# zasilacz_v2.net
KiCad netlist of a schematic drawn in EAGLE
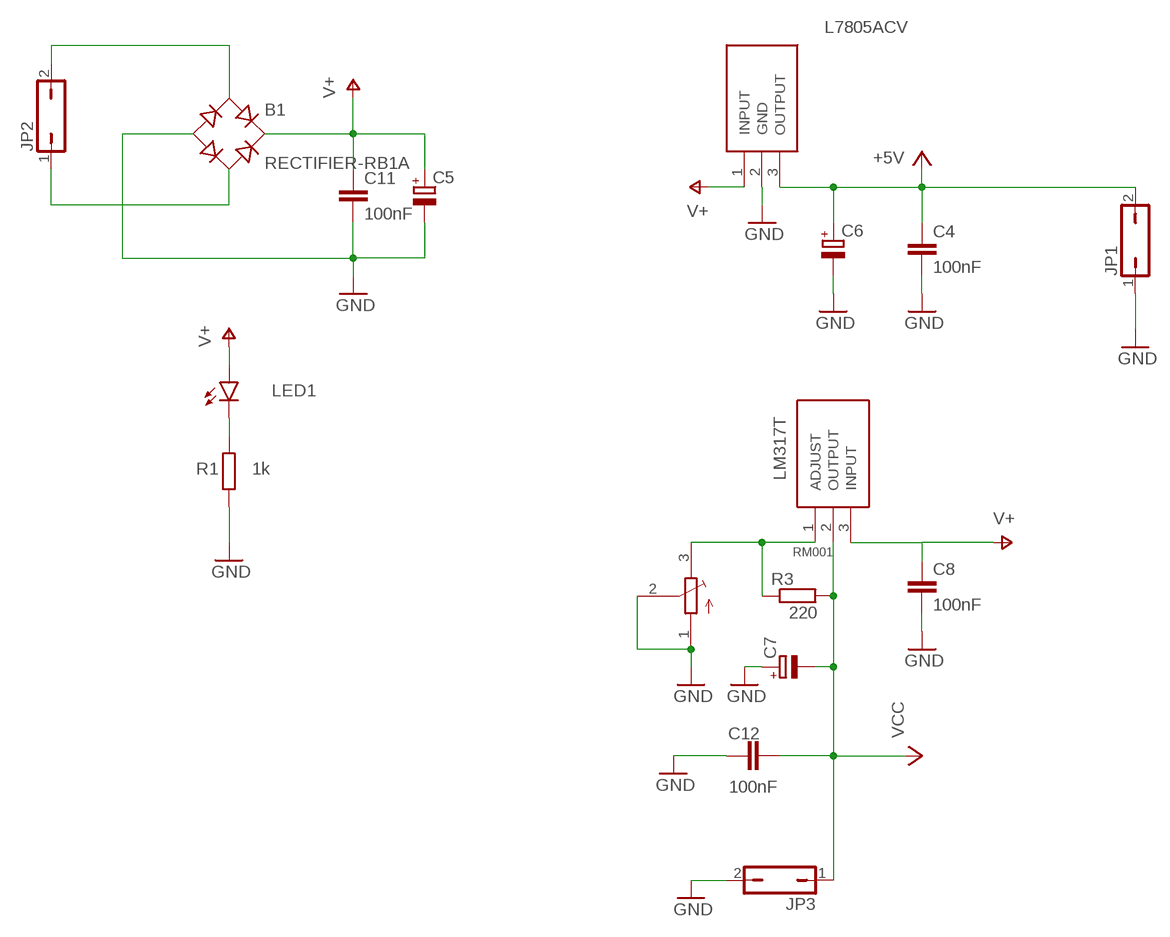
[diagram p0: schematic, sheet 1]

(export (version "E")
  (design (tool "Eeschema 10.0.6"))
  (components
    (comp (ref ",1")
      (value "LM317T")
      (footprint "eagle-import:TO255P460X1020X2008-3P")
      (fields (field (name "MOUSER_PART_NUMBER") "511-LM317T"))
      (libsource (lib "eagle-import") (part "LM317T"))
    )
    (comp (ref "B1")
      (value "RECTIFIER-RB1A")
      (footprint "eagle-import:RB1A")
      (libsource (lib "eagle-import") (part "RECTIFIER-RB1A"))
    )
    (comp (ref "C4")
      (value "100nF")
      (footprint "eagle-import:C025-024X044")
      (libsource (lib "eagle-import") (part "C-EU025-024X044"))
    )
    (comp (ref "C5")
      (value "CPOL-EUE5-10.5")
      (footprint "eagle-import:E5-10,5")
      (libsource (lib "eagle-import") (part "CPOL-EUE5-10.5"))
    )
    (comp (ref "C6")
      (value "CPOL-EUE5-10.5")
      (footprint "eagle-import:E5-10,5")
      (libsource (lib "eagle-import") (part "CPOL-EUE5-10.5"))
    )
    (comp (ref "C7")
      (value "CPOL-EUE5-10.5")
      (footprint "eagle-import:E5-10,5")
      (libsource (lib "eagle-import") (part "CPOL-EUE5-10.5"))
    )
    (comp (ref "C8")
      (value "100nF")
      (footprint "eagle-import:C025-024X044")
      (libsource (lib "eagle-import") (part "C-EU025-024X044"))
    )
    (comp (ref "C11")
      (value "100nF")
      (footprint "eagle-import:C025-024X044")
      (libsource (lib "eagle-import") (part "C-EU025-024X044"))
    )
    (comp (ref "C12")
      (value "100nF")
      (footprint "eagle-import:C025-024X044")
      (libsource (lib "eagle-import") (part "C-EU025-024X044"))
    )
    (comp (ref "IC1")
      (value "L7805ACV")
      (footprint "eagle-import:TO255P460X1020X2008-3P")
      (fields (field (name "MOUSER_PART_NUMBER") "511-L7805ACV"))
      (libsource (lib "eagle-import") (part "L7805ACV"))
    )
    (comp (ref "JP1")
      (value "JP1Q")
      (footprint "eagle-import:JP1")
      (libsource (lib "eagle-import") (part "JP1Q"))
    )
    (comp (ref "JP2")
      (value "JP1Q")
      (footprint "eagle-import:JP1")
      (libsource (lib "eagle-import") (part "JP1Q"))
    )
    (comp (ref "JP3")
      (value "JP1Q")
      (footprint "eagle-import:JP1")
      (libsource (lib "eagle-import") (part "JP1Q"))
    )
    (comp (ref "LED1")
      (value "TLLG4400")
      (footprint "eagle-import:LED3MM")
      (fields (field (name "MF") "VISHAY SEMICONDUCTOR"))
      (libsource (lib "eagle-import") (part "TLLG4400"))
    )
    (comp (ref "R1")
      (value "1k")
      (footprint "eagle-import:0204_5")
      (libsource (lib "eagle-import") (part "R-EU_0204/5"))
    )
    (comp (ref "R3")
      (value "220")
      (footprint "eagle-import:0204_5")
      (libsource (lib "eagle-import") (part "R-EU_0204/5"))
    )
    (comp (ref "RM001")
      (value "RM065")
      (footprint "eagle-import:RM065")
      (fields (field (name "MF") "Vishay") (field (name "MP") "RM-065"))
      (libsource (lib "eagle-import") (part "RM065"))
    )
  )
  (nets
    (net (code "1") (name "+5V") (class "Default")
      (node (ref "C4") (pin "1") (pinfunction "1_1") (pintype "passive"))
      (node (ref "C6") (pin "+") (pinfunction "+_+") (pintype "passive"))
      (node (ref "IC1") (pin "3") (pinfunction "OUTPUT_3") (pintype "bidirectional"))
      (node (ref "JP1") (pin "2") (pinfunction "2_2") (pintype "passive"))
    )
    (net (code "2") (name "GND") (class "Default")
      (node (ref "B1") (pin "-") (pinfunction "-_-") (pintype "passive"))
      (node (ref "C11") (pin "2") (pinfunction "2_2") (pintype "passive"))
      (node (ref "C12") (pin "1") (pinfunction "1_1") (pintype "passive"))
      (node (ref "C4") (pin "2") (pinfunction "2_2") (pintype "passive"))
      (node (ref "C5") (pin "-") (pinfunction "-_-") (pintype "passive"))
      (node (ref "C6") (pin "-") (pinfunction "-_-") (pintype "passive"))
      (node (ref "C7") (pin "+") (pinfunction "+_+") (pintype "passive"))
      (node (ref "C8") (pin "2") (pinfunction "2_2") (pintype "passive"))
      (node (ref "IC1") (pin "2") (pinfunction "GND_2") (pintype "bidirectional"))
      (node (ref "JP1") (pin "1") (pinfunction "1_1") (pintype "passive"))
      (node (ref "JP3") (pin "2") (pinfunction "2_2") (pintype "passive"))
      (node (ref "R1") (pin "1") (pinfunction "1_1") (pintype "passive"))
      (node (ref "RM001") (pin "1") (pinfunction "P$1_1") (pintype "bidirectional"))
      (node (ref "RM001") (pin "2") (pinfunction "P$2_2") (pintype "bidirectional"))
    )
    (net (code "3") (name "Net-(,1-ADJUST)") (class "Default")
      (node (ref ",1") (pin "1") (pinfunction "ADJUST_1") (pintype "bidirectional"))
      (node (ref "R3") (pin "1") (pinfunction "1_1") (pintype "passive"))
      (node (ref "RM001") (pin "3") (pinfunction "P$3_3") (pintype "bidirectional"))
    )
    (net (code "4") (name "Net-(B1-PadAC1)") (class "Default")
      (node (ref "B1") (pin "AC1") (pinfunction "AC1_AC1") (pintype "passive"))
      (node (ref "JP2") (pin "2") (pinfunction "2_2") (pintype "passive"))
    )
    (net (code "5") (name "Net-(B1-PadAC2)") (class "Default")
      (node (ref "B1") (pin "AC2") (pinfunction "AC2_AC2") (pintype "passive"))
      (node (ref "JP2") (pin "1") (pinfunction "1_1") (pintype "passive"))
    )
    (net (code "6") (name "Net-(LED1-C)") (class "Default")
      (node (ref "LED1") (pin "K") (pinfunction "C_K") (pintype "passive"))
      (node (ref "R1") (pin "2") (pinfunction "2_2") (pintype "passive"))
    )
    (net (code "7") (name "V+") (class "Default")
      (node (ref ",1") (pin "3") (pinfunction "INPUT_3") (pintype "bidirectional"))
      (node (ref "B1") (pin "+") (pinfunction "+_+") (pintype "passive"))
      (node (ref "C11") (pin "1") (pinfunction "1_1") (pintype "passive"))
      (node (ref "C5") (pin "+") (pinfunction "+_+") (pintype "passive"))
      (node (ref "C8") (pin "1") (pinfunction "1_1") (pintype "passive"))
      (node (ref "IC1") (pin "1") (pinfunction "INPUT_1") (pintype "bidirectional"))
      (node (ref "LED1") (pin "A") (pinfunction "A_A") (pintype "passive"))
    )
    (net (code "8") (name "VCC") (class "Default")
      (node (ref ",1") (pin "2") (pinfunction "OUTPUT_2") (pintype "bidirectional"))
      (node (ref "C12") (pin "2") (pinfunction "2_2") (pintype "passive"))
      (node (ref "C7") (pin "-") (pinfunction "-_-") (pintype "passive"))
      (node (ref "JP3") (pin "1") (pinfunction "1_1") (pintype "passive"))
      (node (ref "R3") (pin "2") (pinfunction "2_2") (pintype "passive"))
    )
  )
)
